# Microcontroller.net
KiCad netlist of a schematic drawn in Altium Designer
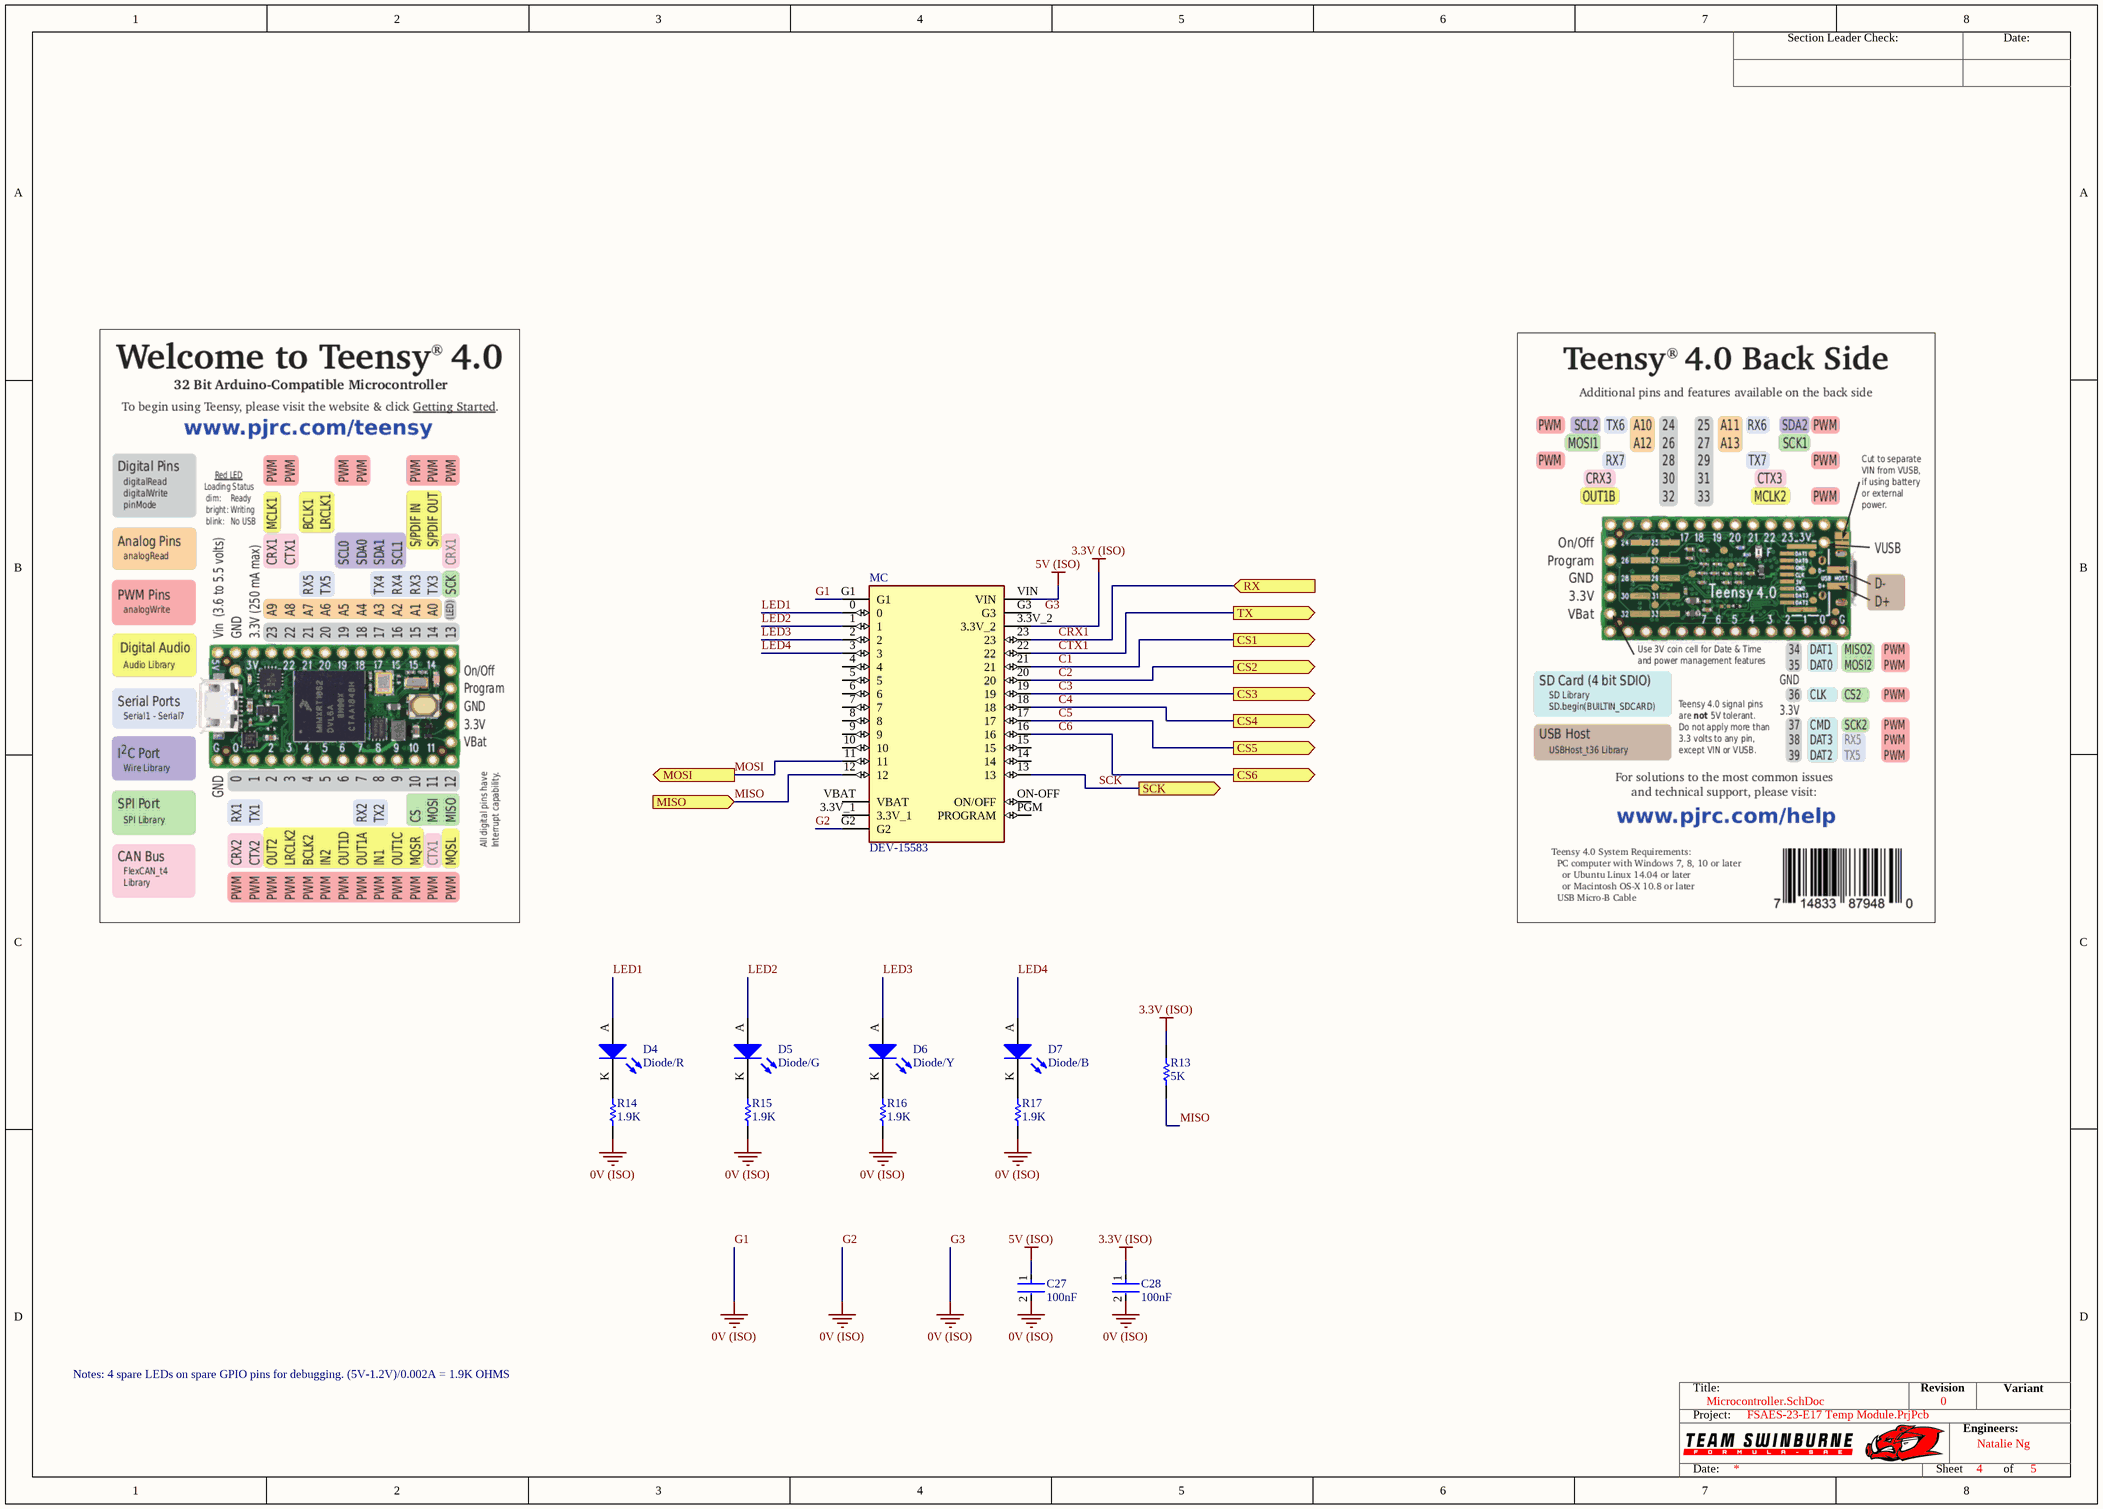
[diagram p0: Microcontroller.SchDoc]

(export (version "E")
  (design (tool "Eeschema 10.0.6"))
  (components
    (comp (ref "C27")
      (value "100nF")
      (footprint "FP-GCM319-0_15-IPC_A")
      (description "CAP CER 10000PF 100V NP0 1206")
      (fields (field (name "TOLERANCE") "5%"))
      (libsource (lib "Team Swinburne") (part "b4654b650e69147ec39a6b967a45e02"))
    )
    (comp (ref "C28")
      (value "100nF")
      (footprint "FP-GCM319-0_15-IPC_A")
      (description "CAP CER 10000PF 100V NP0 1206")
      (fields (field (name "TOLERANCE") "5%"))
      (libsource (lib "Team Swinburne") (part "b4654b650e69147ec39a6b967a45e02"))
    )
    (comp (ref "D4")
      (value "Diode/R")
      (footprint "0805 LED")
      (description "Red LED Indication - Discrete 1.75V 0805 (2012 Metric)")
      (fields (field (name "PART NUMBER") "SML-210LTT86"))
      (libsource (lib "Team Swinburne") (part "LED"))
    )
    (comp (ref "D5")
      (value "Diode/G")
      (footprint "0805 LED")
      (description "Green LED Indication - Discrete 1.75V 0805 (2012 Metric)")
      (fields (field (name "PART NUMBER") "SML-210FTT86"))
      (libsource (lib "Team Swinburne") (part "LED"))
    )
    (comp (ref "D6")
      (value "Diode/Y")
      (footprint "0805 LED")
      (description "Yellow LED Indication - Discrete 1.75V 0805 (2012 Metric)")
      (fields (field (name "PART NUMBER") "SML-211YTT86"))
      (libsource (lib "Team Swinburne") (part "LED"))
    )
    (comp (ref "D7")
      (value "Diode/B")
      (footprint "0805 LED")
      (description "LED BLUE CLEAR 2012 SMD")
      (fields (field (name "PART NUMBER") "SML-MN2BCTT86C"))
      (libsource (lib "Team Swinburne") (part "LED"))
    )
    (comp (ref "MC")
      (value "DEV-15583")
      (footprint "DEV-15583-Footprint-1")
      (description "Teensy 4.0 Microcontroller Board")
      (libsource (lib "Team Swinburne") (part "Teensy 4.0-Symbol-1"))
    )
    (comp (ref "R13")
      (value "5K")
      (footprint "Y16295K00000T9R-Footprint-1")
      (description "RED SMD 5K OHM 1/10W 0805")
      (libsource (lib "Team Swinburne") (part "Y16295K00000T9R-Symbol-1"))
    )
    (comp (ref "R14")
      (value "1.9K")
      (footprint "Y16241K90000T9R-Footprint-1")
      (description "RES SMD 1.9K OHM 1/5W 0805")
      (fields (field (name "TOLERANCE") "0.01%"))
      (libsource (lib "Team Swinburne") (part "Y16241K90000T9R-Symbol-1"))
    )
    (comp (ref "R15")
      (value "1.9K")
      (footprint "Y16241K90000T9R-Footprint-1")
      (description "RES SMD 1.9K OHM 1/5W 0805")
      (fields (field (name "TOLERANCE") "0.01%"))
      (libsource (lib "Team Swinburne") (part "Y16241K90000T9R-Symbol-1"))
    )
    (comp (ref "R16")
      (value "1.9K")
      (footprint "Y16241K90000T9R-Footprint-1")
      (description "RES SMD 1.9K OHM 1/5W 0805")
      (fields (field (name "TOLERANCE") "0.01%"))
      (libsource (lib "Team Swinburne") (part "Y16241K90000T9R-Symbol-1"))
    )
    (comp (ref "R17")
      (value "1.9K")
      (footprint "Y16241K90000T9R-Footprint-1")
      (description "RES SMD 1.9K OHM 1/5W 0805")
      (fields (field (name "TOLERANCE") "0.01%"))
      (libsource (lib "Team Swinburne") (part "Y16241K90000T9R-Symbol-1"))
    )
  )
  (nets
    (net (code "1") (name "/C1") (class "Default")
      (node (ref "MC") (pin "21") (pinfunction "21_21") (pintype "bidirectional"))
    )
    (net (code "2") (name "/C2") (class "Default")
      (node (ref "MC") (pin "20") (pinfunction "20_20") (pintype "bidirectional"))
    )
    (net (code "3") (name "/C3") (class "Default")
      (node (ref "MC") (pin "19") (pinfunction "19_19") (pintype "bidirectional"))
    )
    (net (code "4") (name "/C4") (class "Default")
      (node (ref "MC") (pin "18") (pinfunction "18_18") (pintype "bidirectional"))
    )
    (net (code "5") (name "/C5") (class "Default")
      (node (ref "MC") (pin "17") (pinfunction "17_17") (pintype "bidirectional"))
    )
    (net (code "6") (name "/C6") (class "Default")
      (node (ref "MC") (pin "16") (pinfunction "16_16") (pintype "bidirectional"))
    )
    (net (code "7") (name "/CRX1") (class "Default")
      (node (ref "MC") (pin "23") (pinfunction "23_23") (pintype "bidirectional"))
    )
    (net (code "8") (name "/CTX1") (class "Default")
      (node (ref "MC") (pin "22") (pinfunction "22_22") (pintype "bidirectional"))
    )
    (net (code "9") (name "/LED1") (class "Default")
      (node (ref "D4") (pin "A") (pinfunction "A_A") (pintype "passive"))
      (node (ref "MC") (pin "0") (pinfunction "0_0") (pintype "bidirectional"))
    )
    (net (code "10") (name "/LED2") (class "Default")
      (node (ref "D5") (pin "A") (pinfunction "A_A") (pintype "passive"))
      (node (ref "MC") (pin "1") (pinfunction "1_1") (pintype "bidirectional"))
    )
    (net (code "11") (name "/LED3") (class "Default")
      (node (ref "D6") (pin "A") (pinfunction "A_A") (pintype "passive"))
      (node (ref "MC") (pin "2") (pinfunction "2_2") (pintype "bidirectional"))
    )
    (net (code "12") (name "/LED4") (class "Default")
      (node (ref "D7") (pin "A") (pinfunction "A_A") (pintype "passive"))
      (node (ref "MC") (pin "3") (pinfunction "3_3") (pintype "bidirectional"))
    )
    (net (code "13") (name "/MISO") (class "Default")
      (node (ref "MC") (pin "12") (pinfunction "12_12") (pintype "bidirectional"))
      (node (ref "R13") (pin "1") (pinfunction "1_1") (pintype "passive"))
    )
    (net (code "14") (name "/MOSI") (class "Default")
      (node (ref "MC") (pin "11") (pinfunction "11_11") (pintype "bidirectional"))
    )
    (net (code "15") (name "/SCK") (class "Default")
      (node (ref "MC") (pin "13") (pinfunction "13_13") (pintype "bidirectional"))
    )
    (net (code "16") (name "0V (ISO)") (class "Default")
      (node (ref "C27") (pin "2") (pinfunction "2_2") (pintype "passive"))
      (node (ref "C28") (pin "2") (pinfunction "2_2") (pintype "passive"))
      (node (ref "MC") (pin "G1") (pinfunction "G1_G1") (pintype "power_in"))
      (node (ref "MC") (pin "G2") (pinfunction "G2_G2") (pintype "power_in"))
      (node (ref "R14") (pin "1") (pinfunction "1_1") (pintype "passive"))
      (node (ref "R15") (pin "1") (pinfunction "1_1") (pintype "passive"))
      (node (ref "R16") (pin "1") (pinfunction "1_1") (pintype "passive"))
      (node (ref "R17") (pin "1") (pinfunction "1_1") (pintype "passive"))
    )
    (net (code "17") (name "3.3V (ISO)") (class "Default")
      (node (ref "C28") (pin "1") (pinfunction "1_1") (pintype "passive"))
      (node (ref "MC") (pin "3.3V_2") (pinfunction "3.3V_2_3.3V_2") (pintype "power_in"))
      (node (ref "R13") (pin "2") (pinfunction "2_2") (pintype "passive"))
    )
    (net (code "18") (name "5V (ISO)") (class "Default")
      (node (ref "C27") (pin "1") (pinfunction "1_1") (pintype "passive"))
      (node (ref "MC") (pin "VIN") (pinfunction "VIN_VIN") (pintype "power_in"))
    )
    (net (code "19") (name "Net-(D4-PadK)") (class "Default")
      (node (ref "D4") (pin "K") (pinfunction "K_K") (pintype "passive"))
      (node (ref "R14") (pin "2") (pinfunction "2_2") (pintype "passive"))
    )
    (net (code "20") (name "Net-(D5-PadK)") (class "Default")
      (node (ref "D5") (pin "K") (pinfunction "K_K") (pintype "passive"))
      (node (ref "R15") (pin "2") (pinfunction "2_2") (pintype "passive"))
    )
    (net (code "21") (name "Net-(D6-PadK)") (class "Default")
      (node (ref "D6") (pin "K") (pinfunction "K_K") (pintype "passive"))
      (node (ref "R16") (pin "2") (pinfunction "2_2") (pintype "passive"))
    )
    (net (code "22") (name "Net-(D7-PadK)") (class "Default")
      (node (ref "D7") (pin "K") (pinfunction "K_K") (pintype "passive"))
      (node (ref "R17") (pin "2") (pinfunction "2_2") (pintype "passive"))
    )
    (net (code "23") (name "unconnected-(MC-ON{slash}OFF-PadON-OFF)") (class "Default")
      (node (ref "MC") (pin "ON-OFF") (pinfunction "ON/OFF_ON-OFF") (pintype "bidirectional"))
    )
    (net (code "24") (name "unconnected-(MC-PROGRAM-PadPGM)") (class "Default")
      (node (ref "MC") (pin "PGM") (pinfunction "PROGRAM_PGM") (pintype "bidirectional"))
    )
    (net (code "25") (name "unconnected-(MC-Pad3.3V_1)") (class "Default")
      (node (ref "MC") (pin "3.3V_1") (pinfunction "3.3V_1_3.3V_1") (pintype "power_in"))
    )
    (net (code "26") (name "unconnected-(MC-Pad4)") (class "Default")
      (node (ref "MC") (pin "4") (pinfunction "4_4") (pintype "bidirectional"))
    )
    (net (code "27") (name "unconnected-(MC-Pad5)") (class "Default")
      (node (ref "MC") (pin "5") (pinfunction "5_5") (pintype "bidirectional"))
    )
    (net (code "28") (name "unconnected-(MC-Pad6)") (class "Default")
      (node (ref "MC") (pin "6") (pinfunction "6_6") (pintype "bidirectional"))
    )
    (net (code "29") (name "unconnected-(MC-Pad7)") (class "Default")
      (node (ref "MC") (pin "7") (pinfunction "7_7") (pintype "bidirectional"))
    )
    (net (code "30") (name "unconnected-(MC-Pad8)") (class "Default")
      (node (ref "MC") (pin "8") (pinfunction "8_8") (pintype "bidirectional"))
    )
    (net (code "31") (name "unconnected-(MC-Pad9)") (class "Default")
      (node (ref "MC") (pin "9") (pinfunction "9_9") (pintype "bidirectional"))
    )
    (net (code "32") (name "unconnected-(MC-Pad10)") (class "Default")
      (node (ref "MC") (pin "10") (pinfunction "10_10") (pintype "bidirectional"))
    )
    (net (code "33") (name "unconnected-(MC-Pad14)") (class "Default")
      (node (ref "MC") (pin "14") (pinfunction "14_14") (pintype "bidirectional"))
    )
    (net (code "34") (name "unconnected-(MC-Pad15)") (class "Default")
      (node (ref "MC") (pin "15") (pinfunction "15_15") (pintype "bidirectional"))
    )
    (net (code "35") (name "unconnected-(MC-PadG3)") (class "Default")
      (node (ref "MC") (pin "G3") (pinfunction "G3_G3") (pintype "power_in"))
    )
    (net (code "36") (name "unconnected-(MC-PadVBAT)") (class "Default")
      (node (ref "MC") (pin "VBAT") (pinfunction "VBAT_VBAT") (pintype "power_in"))
    )
  )
)
